# 18_-_POWER.net
KiCad netlist of a schematic drawn in Altium Designer
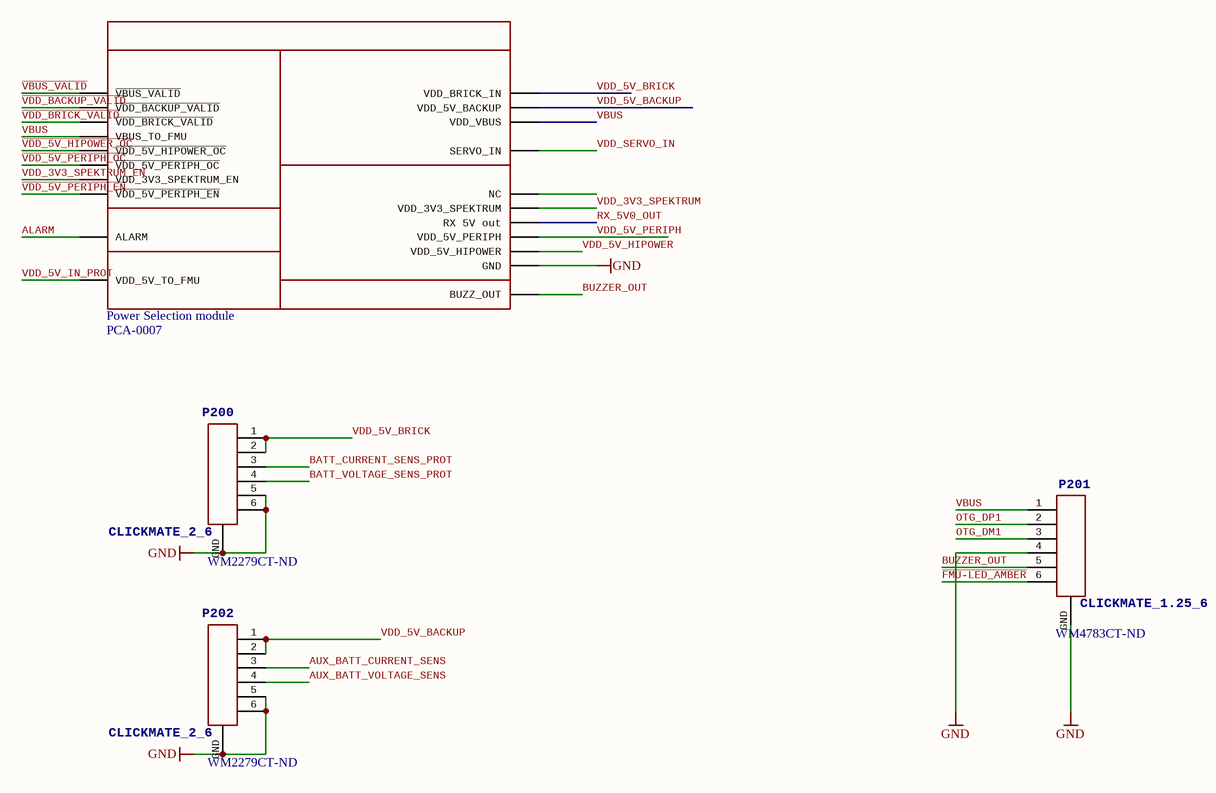
[diagram p0: [18] - POWER.SchDoc]

(export (version "E")
  (design (tool "Eeschema 10.0.6"))
  (components
    (comp (ref "P200")
      (value "CLICKMATE_2_6")
      (footprint "CLICKMATE_V6_2MM")
      (description "Connector, Header, 6Pos, 2.54MM, Vert, THT, Au")
      (fields (field (name "SUPPLIER PART NUMBER 1") "WM2279CT-ND") (field (name "3DR_PARTNO") "PRT0445"))
      (libsource (lib "PCA_0005_FULL_CB_REV_A") (part "CLICKMATE_2_6"))
    )
    (comp (ref "P201")
      (value "CLICKMATE_1.25_6")
      (footprint "CLICKMATE_V6")
      (description "Connector, Rcpt, 6Pos, 1.25MM, W/B, VERT, SMD, Tin")
      (fields (field (name "SUPPLIER PART NUMBER 1") "WM4783CT-ND") (field (name "3DR_PARTNO") "PRT0439"))
      (libsource (lib "PCA_0005_FULL_CB_REV_A") (part "CLICKMATE_1.25_6"))
    )
    (comp (ref "P202")
      (value "CLICKMATE_2_6")
      (footprint "CLICKMATE_V6_2MM")
      (description "Connector, Header, 6Pos, 2.54MM, Vert, THT, Au")
      (fields (field (name "SUPPLIER PART NUMBER 1") "WM2279CT-ND") (field (name "3DR_PARTNO") "PRT0445"))
      (libsource (lib "PCA_0005_FULL_CB_REV_A") (part "CLICKMATE_2_6"))
    )
    (comp (ref "PSM200")
      (value "Power Selection module")
      (footprint "PSM")
      (description "PCA, PSM, PX4, Assembly")
      (fields (field (name "SUPPLIER PART NUMBER 1") "PCA-0007") (field (name "3DR_PARTNO") "PCA0007"))
      (libsource (lib "PCA_0005_FULL_CB_REV_A") (part "PSMPSM"))
    )
  )
  (nets
    (net (code "1") (name "/ALARM") (class "Default")
      (node (ref "PSM200") (pin "ALARM") (pinfunction "ALARM_ALARM") (pintype "passive"))
    )
    (net (code "2") (name "/AUX_BATT_CURRENT_SENS") (class "Default")
      (node (ref "P202") (pin "3") (pinfunction "3_3") (pintype "passive"))
    )
    (net (code "3") (name "/AUX_BATT_VOLTAGE_SENS") (class "Default")
      (node (ref "P202") (pin "4") (pinfunction "4_4") (pintype "passive"))
    )
    (net (code "4") (name "/BATT_CURRENT_SENS_PROT") (class "Default")
      (node (ref "P200") (pin "3") (pinfunction "3_3") (pintype "passive"))
    )
    (net (code "5") (name "/BATT_VOLTAGE_SENS_PROT") (class "Default")
      (node (ref "P200") (pin "4") (pinfunction "4_4") (pintype "passive"))
    )
    (net (code "6") (name "/BUZZER_OUT") (class "Default")
      (node (ref "P201") (pin "5") (pinfunction "5_5") (pintype "passive"))
      (node (ref "PSM200") (pin "BUZZER_OUT") (pinfunction "BUZZ_OUT_BUZZER_OUT") (pintype "passive"))
    )
    (net (code "7") (name "/OTG_DM1") (class "Default")
      (node (ref "P201") (pin "3") (pinfunction "3_3") (pintype "passive"))
    )
    (net (code "8") (name "/OTG_DP1") (class "Default")
      (node (ref "P201") (pin "2") (pinfunction "2_2") (pintype "passive"))
    )
    (net (code "9") (name "/RX_5V0_OUT") (class "Default")
      (node (ref "PSM200") (pin "RX") (pinfunction "RX_5V_out_RX") (pintype "passive"))
    )
    (net (code "10") (name "/VBUS") (class "Default")
      (node (ref "P201") (pin "1") (pinfunction "1_1") (pintype "passive"))
      (node (ref "PSM200") (pin "VBUS") (pinfunction "VBUS_TO_FMU_VBUS") (pintype "passive"))
      (node (ref "PSM200") (pin "VDD_VBUS") (pinfunction "VDD_VBUS_VDD_VBUS") (pintype "passive"))
    )
    (net (code "11") (name "/VDD_3V3_SPEKTRUM") (class "Default")
      (node (ref "PSM200") (pin "SPEK") (pinfunction "VDD_3V3_SPEKTRUM_SPEK") (pintype "passive"))
    )
    (net (code "12") (name "/VDD_3V3_SPEKTRUM_EN") (class "Default")
      (node (ref "PSM200") (pin "VDD_3V3_SPEKTRUM_EN") (pinfunction "VDD_3V3_SPEKTRUM_EN_VDD_3V3_SPEKTRUM_EN") (pintype "passive"))
    )
    (net (code "13") (name "/VDD_5V_BACKUP") (class "Default")
      (node (ref "P202") (pin "1") (pinfunction "1_1") (pintype "passive"))
      (node (ref "P202") (pin "2") (pinfunction "2_2") (pintype "passive"))
      (node (ref "PSM200") (pin "VDD_5V_BACKUP") (pinfunction "VDD_5V_BACKUP_VDD_5V_BACKUP") (pintype "passive"))
    )
    (net (code "14") (name "/VDD_5V_BRICK") (class "Default")
      (node (ref "P200") (pin "1") (pinfunction "1_1") (pintype "passive"))
      (node (ref "P200") (pin "2") (pinfunction "2_2") (pintype "passive"))
      (node (ref "PSM200") (pin "VDD_BRICK_IN") (pinfunction "VDD_BRICK_IN_VDD_BRICK_IN") (pintype "passive"))
    )
    (net (code "15") (name "/VDD_5V_HIPOWER") (class "Default")
      (node (ref "PSM200") (pin "5V_HIPOWER") (pinfunction "VDD_5V_HIPOWER_5V_HIPOWER") (pintype "passive"))
    )
    (net (code "16") (name "/VDD_5V_IN_PROT") (class "Default")
      (node (ref "PSM200") (pin "VDD_5V_IN_PROT") (pinfunction "VDD_5V_TO_FMU_VDD_5V_IN_PROT") (pintype "passive"))
    )
    (net (code "17") (name "/VDD_5V_PERIPH") (class "Default")
      (node (ref "PSM200") (pin "5V_PERIPH") (pinfunction "VDD_5V_PERIPH_5V_PERIPH") (pintype "passive"))
    )
    (net (code "18") (name "/VDD_SERVO_IN") (class "Default")
      (node (ref "PSM200") (pin "SERVO_IN") (pinfunction "SERVO_IN_SERVO_IN") (pintype "passive"))
    )
    (net (code "19") (name "/~{FMU-LED_AMBER}") (class "Default")
      (node (ref "P201") (pin "6") (pinfunction "6_6") (pintype "passive"))
    )
    (net (code "20") (name "/~{VBUS_VALID}") (class "Default")
      (node (ref "PSM200") (pin "!VBUS_VALID") (pinfunction "~{VBUS_VALID}_!VBUS_VALID") (pintype "passive"))
    )
    (net (code "21") (name "/~{VDD_5V_HIPOWER_OC}") (class "Default")
      (node (ref "PSM200") (pin "!VDD_5V_HIPOWER_OC") (pinfunction "~{VDD_5V_HIPOWER_OC}_!VDD_5V_HIPOWER_OC") (pintype "passive"))
    )
    (net (code "22") (name "/~{VDD_5V_PERIPH_EN}") (class "Default")
      (node (ref "PSM200") (pin "!VDD_5V_PERIPH_EN") (pinfunction "~{VDD_5V_PERIPH_EN}_!VDD_5V_PERIPH_EN") (pintype "passive"))
    )
    (net (code "23") (name "/~{VDD_5V_PERIPH_OC}") (class "Default")
      (node (ref "PSM200") (pin "!VDD_5V_PERIPH_OC") (pinfunction "~{VDD_5V_PERIPH_OC}_!VDD_5V_PERIPH_OC") (pintype "passive"))
    )
    (net (code "24") (name "/~{VDD_BACKUP_VALID}") (class "Default")
      (node (ref "PSM200") (pin "!VDD_BACKUP_VALID") (pinfunction "~{VDD_BACKUP_VALID}_!VDD_BACKUP_VALID") (pintype "passive"))
    )
    (net (code "25") (name "/~{VDD_BRICK_VALID}") (class "Default")
      (node (ref "PSM200") (pin "!VDD_BRICK_VALID") (pinfunction "~{VDD_BRICK_VALID}_!VDD_BRICK_VALID") (pintype "passive"))
    )
    (net (code "26") (name "GND") (class "Default")
      (node (ref "P200") (pin "5") (pinfunction "5_5") (pintype "passive"))
      (node (ref "P200") (pin "6") (pinfunction "6_6") (pintype "passive"))
      (node (ref "P200") (pin "GND") (pinfunction "GND_GND") (pintype "passive"))
      (node (ref "P201") (pin "4") (pinfunction "4_4") (pintype "passive"))
      (node (ref "P201") (pin "GND") (pinfunction "GND_GND") (pintype "passive"))
      (node (ref "P202") (pin "5") (pinfunction "5_5") (pintype "passive"))
      (node (ref "P202") (pin "6") (pinfunction "6_6") (pintype "passive"))
      (node (ref "P202") (pin "GND") (pinfunction "GND_GND") (pintype "passive"))
      (node (ref "PSM200") (pin "GND") (pinfunction "GND_GND") (pintype "passive"))
    )
    (net (code "27") (name "unconnected-(PSM200-PadNC)") (class "Default")
      (node (ref "PSM200") (pin "NC") (pinfunction "NC_NC") (pintype "passive"))
    )
  )
)
